# PG3_SHEET1.net
KiCad netlist of a schematic drawn in Altium Designer
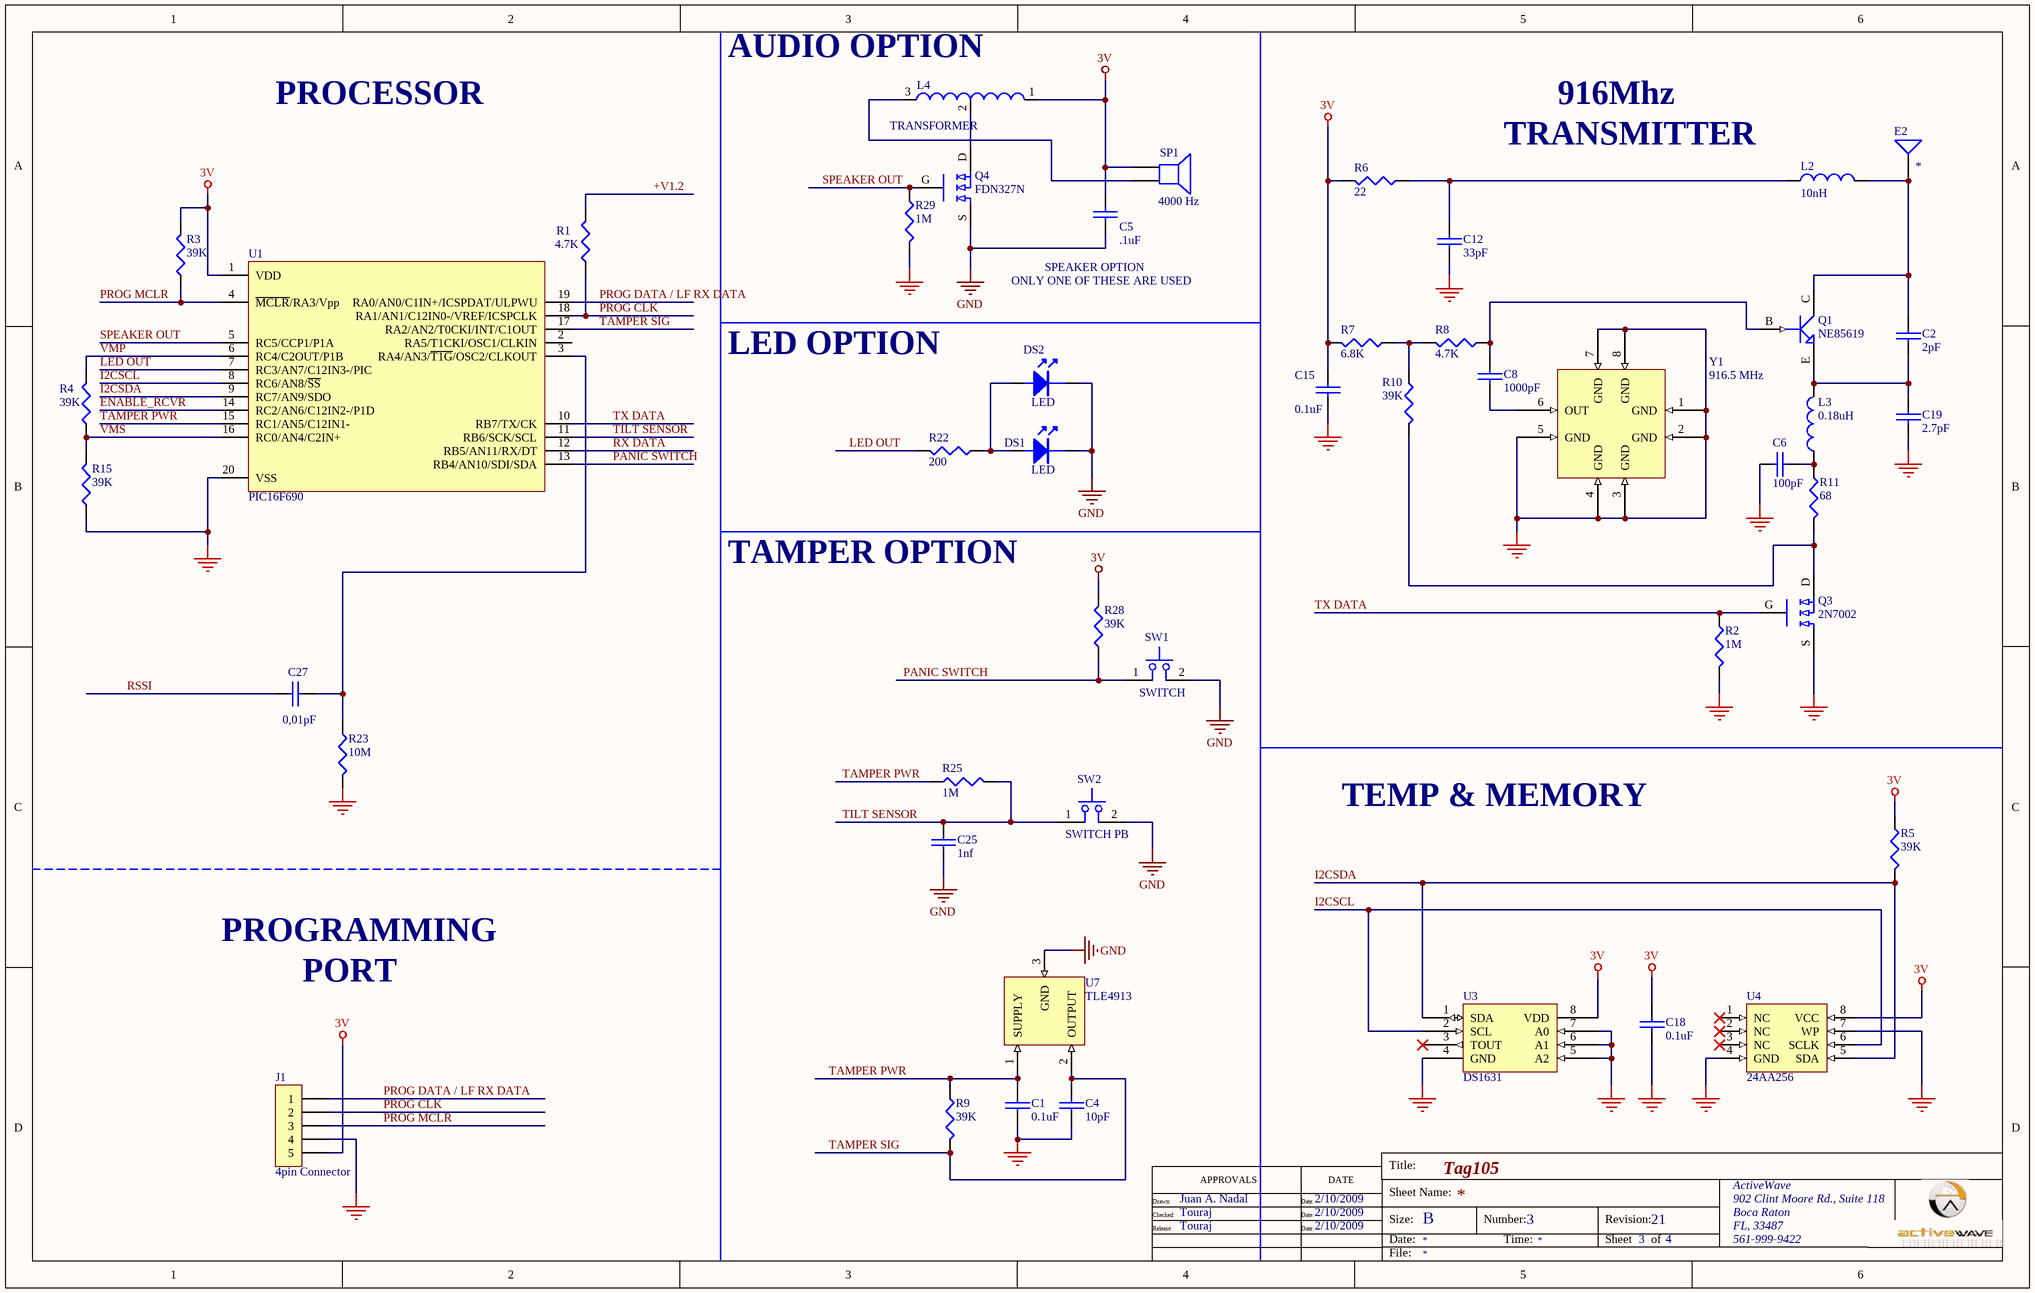
[diagram p0: PG3 SHEET1.schdoc]

(export (version "E")
  (design (tool "Eeschema 10.0.6"))
  (components
    (comp (ref "C1")
      (value "0.1uF")
      (footprint "0603")
      (description "Capacitor")
      (libsource (lib "ActiveWave MasterLib") (part "CAP-0603"))
    )
    (comp (ref "C2")
      (value "2pF")
      (footprint "0603")
      (description "Capacitor")
      (libsource (lib "ActiveWave MasterLib") (part "CAP-0603"))
    )
    (comp (ref "C4")
      (value "10pF")
      (footprint "0603")
      (description "Capacitor")
      (libsource (lib "ActiveWave MasterLib") (part "CAP-0603"))
    )
    (comp (ref "C5")
      (value ".1uF")
      (footprint "0603")
      (description "Capacitor")
      (libsource (lib "ActiveWave MasterLib") (part "CAP-0603"))
    )
    (comp (ref "C6")
      (value "100pF")
      (footprint "0603")
      (description "Capacitor")
      (libsource (lib "ActiveWave MasterLib") (part "CAP-0603"))
    )
    (comp (ref "C8")
      (value "1000pF")
      (footprint "0603")
      (description "Capacitor")
      (libsource (lib "ActiveWave MasterLib") (part "CAP-0603"))
    )
    (comp (ref "C12")
      (value "33pF")
      (footprint "0603")
      (description "Capacitor")
      (libsource (lib "ActiveWave MasterLib") (part "CAP-0603"))
    )
    (comp (ref "C15")
      (value "0.1uF")
      (footprint "0603")
      (description "Capacitor")
      (libsource (lib "ActiveWave MasterLib") (part "CAP-0603"))
    )
    (comp (ref "C18")
      (value "0.1uF")
      (footprint "0603")
      (description "Capacitor")
      (libsource (lib "ActiveWave MasterLib") (part "CAP-0603"))
    )
    (comp (ref "C19")
      (value "2.7pF")
      (footprint "0603")
      (description "Capacitor")
      (libsource (lib "ActiveWave MasterLib") (part "CAP-0603"))
    )
    (comp (ref "C25")
      (value "1nf")
      (footprint "0603")
      (description "Capacitor")
      (libsource (lib "ActiveWave MasterLib") (part "CAP-0603"))
    )
    (comp (ref "C27")
      (value "0,01pF")
      (footprint "0603")
      (description "Capacitor")
      (libsource (lib "ActiveWave MasterLib") (part "CAP-0603"))
    )
    (comp (ref "DS1")
      (value "LED")
      (footprint "404-1032-2-ND")
      (libsource (lib "ActiveWave MasterLib") (part "LED"))
    )
    (comp (ref "DS2")
      (value "LED")
      (footprint "LCE-358RP")
      (description "X-Bring Red Power SMD LED Emitter")
      (fields (field (name "MANUFACTURER") "L.C. LED"))
      (libsource (lib "ActiveWave MasterLib") (part "LCE-358RP"))
    )
    (comp (ref "E2")
      (value "*")
      (footprint "Antenna1")
      (fields (field (name "ALTIUM_VALUE") "*"))
      (libsource (lib "ActiveWave MasterLib") (part "Antenna1"))
    )
    (comp (ref "J1")
      (value "4pin Connector")
      (footprint "1X5 HEADER")
      (description "Connector")
      (libsource (lib "ActiveWave MasterLib") (part "CON5-1"))
    )
    (comp (ref "L2")
      (value "10nH")
      (footprint "0603")
      (libsource (lib "ActiveWave MasterLib") (part "INDUCTOR"))
    )
    (comp (ref "L3")
      (value "0.18uH")
      (footprint "0603")
      (libsource (lib "ActiveWave MasterLib") (part "INDUCTOR"))
    )
    (comp (ref "L4")
      (value "TRANSFORMER")
      (footprint "COIL_6mmx6mm_011012")
      (libsource (lib "ActiveWave MasterLib") (part "INDUCTOR_V2"))
    )
    (comp (ref "Q1")
      (value "NE85619")
      (footprint "3 PIN ULTRA SUPER MINI MOLD")
      (description "TRANSISTOR NPN 1GHZ SMD")
      (fields (field (name "MANUFACTURER") "??????"))
      (libsource (lib "ActiveWave MasterLib") (part "NE85619"))
    )
    (comp (ref "Q3")
      (value "2N7002")
      (footprint "SOT23 FET")
      (description "N-CHANNEL ENHANCEMENT MODE FIELD EFFECT TRANSISTOR")
      (fields (field (name "MANUFACTURER") "FAIRCHILD"))
      (libsource (lib "ActiveWave MasterLib") (part "2N7002"))
    )
    (comp (ref "Q4")
      (value "FDN327N")
      (footprint "SOT23 FET")
      (description "20V N-Channel MOSFET")
      (fields (field (name "MANUFACTURER") "FAIRCHILD"))
      (libsource (lib "ActiveWave MasterLib") (part "FDN327N"))
    )
    (comp (ref "R1") (value "4.7K") (footprint "0603") (libsource (lib "*") (part "RESISTOR")))
    (comp (ref "R2") (value "1M") (libsource (lib "ActiveWave MasterLib") (part "RES-0402")))
    (comp (ref "R3")
      (value "39K")
      (footprint "0603")
      (libsource (lib "ActiveWave MasterLib") (part "RES-0603"))
    )
    (comp (ref "R4")
      (value "39K")
      (footprint "0603")
      (libsource (lib "ActiveWave MasterLib") (part "RES-0603"))
    )
    (comp (ref "R5")
      (value "39K")
      (footprint "0603")
      (libsource (lib "ActiveWave MasterLib") (part "RES-0603"))
    )
    (comp (ref "R6") (value "22") (libsource (lib "ActiveWave MasterLib") (part "RES-0402")))
    (comp (ref "R7") (value "6.8K") (libsource (lib "ActiveWave MasterLib") (part "RES-0402")))
    (comp (ref "R8") (value "4.7K") (libsource (lib "ActiveWave MasterLib") (part "RES-0402")))
    (comp (ref "R9")
      (value "39K")
      (footprint "0603")
      (libsource (lib "ActiveWave MasterLib") (part "RES-0603"))
    )
    (comp (ref "R10")
      (value "39K")
      (footprint "0603")
      (libsource (lib "ActiveWave MasterLib") (part "RES-0603"))
    )
    (comp (ref "R11") (value "68") (libsource (lib "ActiveWave MasterLib") (part "RES-0402")))
    (comp (ref "R15")
      (value "39K")
      (footprint "0603")
      (libsource (lib "ActiveWave MasterLib") (part "RES-0603"))
    )
    (comp (ref "R22")
      (value "200")
      (footprint "0603")
      (libsource (lib "ActiveWave MasterLib") (part "RES-0603"))
    )
    (comp (ref "R23")
      (value "10M")
      (footprint "0603")
      (libsource (lib "ActiveWave MasterLib") (part "RES-0603"))
    )
    (comp (ref "R25")
      (value "1M")
      (footprint "0603")
      (libsource (lib "ActiveWave MasterLib") (part "RES-0603"))
    )
    (comp (ref "R28")
      (value "39K")
      (footprint "0603")
      (libsource (lib "ActiveWave MasterLib") (part "RES-0603"))
    )
    (comp (ref "R29")
      (value "1M")
      (footprint "0603")
      (libsource (lib "ActiveWave MasterLib") (part "RES-0402"))
    )
    (comp (ref "SP1")
      (value "4000 Hz")
      (footprint "SPEAKER 12mmx12mm_011012")
      (description "Surface Mount Transducer")
      (fields (field (name "MANUFACTURER") "PUI Audio"))
      (libsource (lib "ActiveWave MasterLib") (part "SMT-1028-S-R"))
    )
    (comp (ref "SW1")
      (value "SWITCH")
      (footprint "SWITCH PB REVERSED_082907")
      (libsource (lib "ActiveWave MasterLib") (part "SWITCH"))
    )
    (comp (ref "SW2")
      (value "SWITCH PB")
      (footprint "SQ-SEN-DUAL1")
      (libsource (lib "ActiveWave MasterLib") (part "SWITCH PB"))
    )
    (comp (ref "U1")
      (value "PIC16F690")
      (footprint "SSOP20 WIDE")
      (description "Microcontrollers (MCU) 7KB FL 256R 18 I/O")
      (fields (field (name "MANUFACTURER") "Microchip"))
      (libsource (lib "ActiveWave MasterLib") (part "PIC16F690-E/P"))
    )
    (comp (ref "U3")
      (value "DS1631")
      (footprint "SO8 SMALL")
      (description "High-Precision Digital Thermometer and Thermostat")
      (fields (field (name "MANUFACTURER") "DALLAS SEMICONDUCTOR"))
      (libsource (lib "ActiveWave MasterLib") (part "DS1631"))
    )
    (comp (ref "U4")
      (value "24AA256")
      (footprint "SO8")
      (description "24AA256 32k Microchip Serial EEPROM")
      (fields (field (name "MANUFACTURER") "Microchip"))
      (libsource (lib "ActiveWave MasterLib") (part "24AA256-I/P"))
    )
    (comp (ref "U7")
      (value "TLE4913")
      (footprint "SOT23W")
      (description "Low Power Hall Switch")
      (fields (field (name "MANUFACTURER") "Infineon Technologies AG"))
      (libsource (lib "ActiveWave MasterLib") (part "TLE4913"))
    )
    (comp (ref "Y1")
      (value "916.5 MHz")
      (footprint "RESONATOR")
      (description "916.5 MHz Saw Resonator")
      (fields (field (name "MANUFACTURER") "??????"))
      (libsource (lib "ActiveWave MasterLib") (part "RESONATOR"))
    )
  )
  (nets
    (net (code "1") (name "/+V1.2") (class "Default")
      (node (ref "R1") (pin "2") (pinfunction "2_2") (pintype "passive"))
    )
    (net (code "2") (name "/ENABLE_RCVR") (class "Default")
      (node (ref "U1") (pin "14") (pinfunction "RC2/AN6/C12IN2-/P1D_14") (pintype "passive"))
    )
    (net (code "3") (name "/I2CSCL") (class "Default")
      (node (ref "U1") (pin "8") (pinfunction "RC6/AN8/~{SS}_8") (pintype "passive"))
      (node (ref "U3") (pin "2") (pinfunction "SCL_2") (pintype "input"))
      (node (ref "U4") (pin "6") (pinfunction "SCLK_6") (pintype "input"))
    )
    (net (code "4") (name "/I2CSDA") (class "Default")
      (node (ref "R5") (pin "2") (pinfunction "2_2") (pintype "passive"))
      (node (ref "U1") (pin "9") (pinfunction "RC7/AN9/SDO_9") (pintype "passive"))
      (node (ref "U3") (pin "1") (pinfunction "SDA_1") (pintype "bidirectional"))
      (node (ref "U4") (pin "5") (pinfunction "SDA_5") (pintype "input"))
    )
    (net (code "5") (name "/LED OUT") (class "Default")
      (node (ref "R22") (pin "2") (pinfunction "2_2") (pintype "passive"))
      (node (ref "U1") (pin "7") (pinfunction "RC3/AN7/C12IN3-/PIC_7") (pintype "passive"))
    )
    (net (code "6") (name "/PANIC SWITCH") (class "Default")
      (node (ref "R28") (pin "1") (pinfunction "1_1") (pintype "passive"))
      (node (ref "SW1") (pin "1") (pinfunction "1_1") (pintype "passive"))
      (node (ref "U1") (pin "13") (pinfunction "RB4/AN10/SDI/SDA_13") (pintype "passive"))
    )
    (net (code "7") (name "/PROG CLK") (class "Default")
      (node (ref "J1") (pin "2") (pinfunction "2_2") (pintype "passive"))
      (node (ref "R1") (pin "1") (pinfunction "1_1") (pintype "passive"))
      (node (ref "U1") (pin "18") (pinfunction "RA1/AN1/C12IN0-/VREF/ICSPCLK_18") (pintype "passive"))
    )
    (net (code "8") (name "/PROG DATA {slash} LF RX DATA") (class "Default")
      (node (ref "J1") (pin "1") (pinfunction "1_1") (pintype "passive"))
      (node (ref "U1") (pin "19") (pinfunction "RA0/AN0/C1IN+/ICSPDAT/ULPWU_19") (pintype "passive"))
    )
    (net (code "9") (name "/PROG MCLR") (class "Default")
      (node (ref "J1") (pin "3") (pinfunction "3_3") (pintype "passive"))
      (node (ref "R3") (pin "1") (pinfunction "1_1") (pintype "passive"))
      (node (ref "U1") (pin "4") (pinfunction "~{MCLR}/RA3/Vpp_4") (pintype "passive"))
    )
    (net (code "10") (name "/RSSI") (class "Default")
      (node (ref "C27") (pin "1") (pinfunction "1_1") (pintype "passive"))
    )
    (net (code "11") (name "/RX DATA") (class "Default")
      (node (ref "U1") (pin "12") (pinfunction "RB5/AN11/RX/DT_12") (pintype "passive"))
    )
    (net (code "12") (name "/SPEAKER OUT") (class "Default")
      (node (ref "Q4") (pin "G") (pinfunction "G_G") (pintype "passive"))
      (node (ref "R29") (pin "1") (pinfunction "1_1") (pintype "passive"))
      (node (ref "U1") (pin "5") (pinfunction "RC5/CCP1/P1A_5") (pintype "passive"))
    )
    (net (code "13") (name "/TAMPER PWR") (class "Default")
      (node (ref "C1") (pin "1") (pinfunction "1_1") (pintype "passive"))
      (node (ref "R25") (pin "1") (pinfunction "1_1") (pintype "passive"))
      (node (ref "R9") (pin "1") (pinfunction "1_1") (pintype "passive"))
      (node (ref "U1") (pin "15") (pinfunction "RC1/AN5/C12IN1-_15") (pintype "passive"))
      (node (ref "U7") (pin "1") (pinfunction "SUPPLY_1") (pintype "input"))
    )
    (net (code "14") (name "/TAMPER SIG") (class "Default")
      (node (ref "C4") (pin "1") (pinfunction "1_1") (pintype "passive"))
      (node (ref "R9") (pin "2") (pinfunction "2_2") (pintype "passive"))
      (node (ref "U1") (pin "17") (pinfunction "RA2/AN2/T0CKI/INT/C1OUT_17") (pintype "passive"))
      (node (ref "U7") (pin "2") (pinfunction "OUTPUT_2") (pintype "input"))
    )
    (net (code "15") (name "/TILT SENSOR") (class "Default")
      (node (ref "C25") (pin "1") (pinfunction "1_1") (pintype "passive"))
      (node (ref "R25") (pin "2") (pinfunction "2_2") (pintype "passive"))
      (node (ref "SW2") (pin "1") (pinfunction "1_1") (pintype "passive"))
      (node (ref "U1") (pin "11") (pinfunction "RB6/SCK/SCL_11") (pintype "passive"))
    )
    (net (code "16") (name "/TX DATA") (class "Default")
      (node (ref "Q3") (pin "G") (pinfunction "G_G") (pintype "passive"))
      (node (ref "R2") (pin "1") (pinfunction "1_1") (pintype "passive"))
      (node (ref "U1") (pin "10") (pinfunction "RB7/TX/CK_10") (pintype "passive"))
    )
    (net (code "17") (name "/VMP") (class "Default")
      (node (ref "R4") (pin "2") (pinfunction "2_2") (pintype "passive"))
      (node (ref "U1") (pin "6") (pinfunction "RC4/C2OUT/P1B_6") (pintype "passive"))
    )
    (net (code "18") (name "/VMS") (class "Default")
      (node (ref "R15") (pin "2") (pinfunction "2_2") (pintype "passive"))
      (node (ref "R4") (pin "1") (pinfunction "1_1") (pintype "passive"))
      (node (ref "U1") (pin "16") (pinfunction "RC0/AN4/C2IN+_16") (pintype "passive"))
    )
    (net (code "19") (name "3V") (class "Default")
      (node (ref "C15") (pin "1") (pinfunction "1_1") (pintype "passive"))
      (node (ref "C18") (pin "1") (pinfunction "1_1") (pintype "passive"))
      (node (ref "C5") (pin "1") (pinfunction "1_1") (pintype "passive"))
      (node (ref "J1") (pin "5") (pinfunction "5_5") (pintype "passive"))
      (node (ref "L4") (pin "1") (pinfunction "1_1") (pintype "passive"))
      (node (ref "R28") (pin "2") (pinfunction "2_2") (pintype "passive"))
      (node (ref "R3") (pin "2") (pinfunction "2_2") (pintype "passive"))
      (node (ref "R5") (pin "1") (pinfunction "1_1") (pintype "passive"))
      (node (ref "R6") (pin "2") (pinfunction "2_2") (pintype "passive"))
      (node (ref "R7") (pin "2") (pinfunction "2_2") (pintype "passive"))
      (node (ref "SP1") (pin "1") (pinfunction "1_1") (pintype "passive"))
      (node (ref "U1") (pin "1") (pinfunction "VDD_1") (pintype "passive"))
      (node (ref "U3") (pin "8") (pinfunction "VDD_8") (pintype "power_in"))
      (node (ref "U4") (pin "8") (pinfunction "VCC_8") (pintype "input"))
    )
    (net (code "20") (name "GND") (class "Default")
      (node (ref "C1") (pin "2") (pinfunction "2_2") (pintype "passive"))
      (node (ref "C12") (pin "2") (pinfunction "2_2") (pintype "passive"))
      (node (ref "C15") (pin "2") (pinfunction "2_2") (pintype "passive"))
      (node (ref "C18") (pin "2") (pinfunction "2_2") (pintype "passive"))
      (node (ref "C19") (pin "2") (pinfunction "2_2") (pintype "passive"))
      (node (ref "C25") (pin "2") (pinfunction "2_2") (pintype "passive"))
      (node (ref "C4") (pin "2") (pinfunction "2_2") (pintype "passive"))
      (node (ref "C5") (pin "2") (pinfunction "2_2") (pintype "passive"))
      (node (ref "C6") (pin "2") (pinfunction "2_2") (pintype "passive"))
      (node (ref "DS1") (pin "K") (pinfunction "K_K") (pintype "passive"))
      (node (ref "DS2") (pin "2") (pinfunction "2_2") (pintype "passive"))
      (node (ref "J1") (pin "4") (pinfunction "4_4") (pintype "passive"))
      (node (ref "Q3") (pin "S") (pinfunction "S_S") (pintype "passive"))
      (node (ref "Q4") (pin "S") (pinfunction "S_S") (pintype "passive"))
      (node (ref "R15") (pin "1") (pinfunction "1_1") (pintype "passive"))
      (node (ref "R2") (pin "2") (pinfunction "2_2") (pintype "passive"))
      (node (ref "R23") (pin "2") (pinfunction "2_2") (pintype "passive"))
      (node (ref "R29") (pin "2") (pinfunction "2_2") (pintype "passive"))
      (node (ref "SW1") (pin "2") (pinfunction "2_2") (pintype "passive"))
      (node (ref "SW2") (pin "2") (pinfunction "2_2") (pintype "passive"))
      (node (ref "U1") (pin "20") (pinfunction "VSS_20") (pintype "passive"))
      (node (ref "U3") (pin "4") (pinfunction "GND_4") (pintype "power_in"))
      (node (ref "U3") (pin "5") (pinfunction "A2_5") (pintype "input"))
      (node (ref "U3") (pin "6") (pinfunction "A1_6") (pintype "input"))
      (node (ref "U3") (pin "7") (pinfunction "A0_7") (pintype "input"))
      (node (ref "U4") (pin "4") (pinfunction "GND_4") (pintype "input"))
      (node (ref "U4") (pin "7") (pinfunction "WP_7") (pintype "input"))
      (node (ref "U7") (pin "3") (pinfunction "GND_3") (pintype "input"))
      (node (ref "Y1") (pin "1") (pinfunction "GND_1") (pintype "input"))
      (node (ref "Y1") (pin "2") (pinfunction "GND_2") (pintype "input"))
      (node (ref "Y1") (pin "3") (pinfunction "GND_3") (pintype "input"))
      (node (ref "Y1") (pin "4") (pinfunction "GND_4") (pintype "input"))
      (node (ref "Y1") (pin "5") (pinfunction "GND_5") (pintype "input"))
      (node (ref "Y1") (pin "7") (pinfunction "GND_7") (pintype "input"))
      (node (ref "Y1") (pin "8") (pinfunction "GND_8") (pintype "input"))
    )
    (net (code "21") (name "Net-(C2-Pad1)") (class "Default")
      (node (ref "C2") (pin "1") (pinfunction "1_1") (pintype "passive"))
      (node (ref "E2") (pin "1") (pinfunction "1_1") (pintype "passive"))
      (node (ref "L2") (pin "2") (pinfunction "2_2") (pintype "passive"))
      (node (ref "Q1") (pin "C") (pinfunction "C_C") (pintype "passive"))
    )
    (net (code "22") (name "Net-(C6-Pad1)") (class "Default")
      (node (ref "C6") (pin "1") (pinfunction "1_1") (pintype "passive"))
      (node (ref "L3") (pin "1") (pinfunction "1_1") (pintype "passive"))
      (node (ref "R11") (pin "1") (pinfunction "1_1") (pintype "passive"))
    )
    (net (code "23") (name "Net-(C8-Pad1)") (class "Default")
      (node (ref "C8") (pin "1") (pinfunction "1_1") (pintype "passive"))
      (node (ref "Q1") (pin "B") (pinfunction "B_B") (pintype "input"))
      (node (ref "R8") (pin "1") (pinfunction "1_1") (pintype "passive"))
    )
    (net (code "24") (name "Net-(C12-Pad1)") (class "Default")
      (node (ref "C12") (pin "1") (pinfunction "1_1") (pintype "passive"))
      (node (ref "L2") (pin "1") (pinfunction "1_1") (pintype "passive"))
      (node (ref "R6") (pin "1") (pinfunction "1_1") (pintype "passive"))
    )
    (net (code "25") (name "Net-(C19-Pad1)") (class "Default")
      (node (ref "C19") (pin "1") (pinfunction "1_1") (pintype "passive"))
      (node (ref "C2") (pin "2") (pinfunction "2_2") (pintype "passive"))
      (node (ref "L3") (pin "2") (pinfunction "2_2") (pintype "passive"))
      (node (ref "Q1") (pin "E") (pinfunction "E_E") (pintype "passive"))
    )
    (net (code "26") (name "Net-(DS1-PadA)") (class "Default")
      (node (ref "DS1") (pin "A") (pinfunction "A_A") (pintype "passive"))
      (node (ref "DS2") (pin "1") (pinfunction "1_1") (pintype "passive"))
      (node (ref "R22") (pin "1") (pinfunction "1_1") (pintype "passive"))
    )
    (net (code "27") (name "Net-(L4-Pad2)") (class "Default")
      (node (ref "L4") (pin "2") (pinfunction "2_2") (pintype "passive"))
      (node (ref "Q4") (pin "D") (pinfunction "D_D") (pintype "passive"))
    )
    (net (code "28") (name "Net-(L4-Pad3)") (class "Default")
      (node (ref "L4") (pin "3") (pinfunction "3_3") (pintype "passive"))
      (node (ref "SP1") (pin "2") (pinfunction "2_2") (pintype "passive"))
    )
    (net (code "29") (name "Net-(Q3-PadD)") (class "Default")
      (node (ref "Q3") (pin "D") (pinfunction "D_D") (pintype "passive"))
      (node (ref "R10") (pin "2") (pinfunction "2_2") (pintype "passive"))
      (node (ref "R11") (pin "2") (pinfunction "2_2") (pintype "passive"))
    )
    (net (code "30") (name "Net-(R10-Pad1)") (class "Default")
      (node (ref "R10") (pin "1") (pinfunction "1_1") (pintype "passive"))
      (node (ref "R7") (pin "1") (pinfunction "1_1") (pintype "passive"))
      (node (ref "R8") (pin "2") (pinfunction "2_2") (pintype "passive"))
    )
    (net (code "31") (name "Net-(U1-RA4{slash}AN3{slash}~{T1G}{slash}OSC2{slash}CLKOUT)") (class "Default")
      (node (ref "C27") (pin "2") (pinfunction "2_2") (pintype "passive"))
      (node (ref "R23") (pin "1") (pinfunction "1_1") (pintype "passive"))
      (node (ref "U1") (pin "3") (pinfunction "RA4/AN3/~{T1G}/OSC2/CLKOUT_3") (pintype "passive"))
    )
    (net (code "32") (name "Net-(Y1-OUT)") (class "Default")
      (node (ref "C8") (pin "2") (pinfunction "2_2") (pintype "passive"))
      (node (ref "Y1") (pin "6") (pinfunction "OUT_6") (pintype "input"))
    )
    (net (code "33") (name "unconnected-(U1-RA5{slash}T1CKI{slash}OSC1{slash}CLKIN-Pad2)") (class "Default")
      (node (ref "U1") (pin "2") (pinfunction "RA5/T1CKI/OSC1/CLKIN_2") (pintype "passive"))
    )
    (net (code "34") (name "unconnected-(U3-TOUT-Pad3)") (class "Default")
      (node (ref "U3") (pin "3") (pinfunction "TOUT_3") (pintype "output+no_connect"))
    )
    (net (code "35") (name "unconnected-(U4-NC-Pad1)") (class "Default")
      (node (ref "U4") (pin "1") (pinfunction "NC_1") (pintype "input+no_connect"))
    )
    (net (code "36") (name "unconnected-(U4-NC-Pad2)") (class "Default")
      (node (ref "U4") (pin "2") (pinfunction "NC_2") (pintype "input+no_connect"))
    )
    (net (code "37") (name "unconnected-(U4-NC-Pad3)") (class "Default")
      (node (ref "U4") (pin "3") (pinfunction "NC_3") (pintype "input+no_connect"))
    )
  )
)
